# Propulsion_Shield.net
KiCad netlist of a schematic drawn in EAGLE
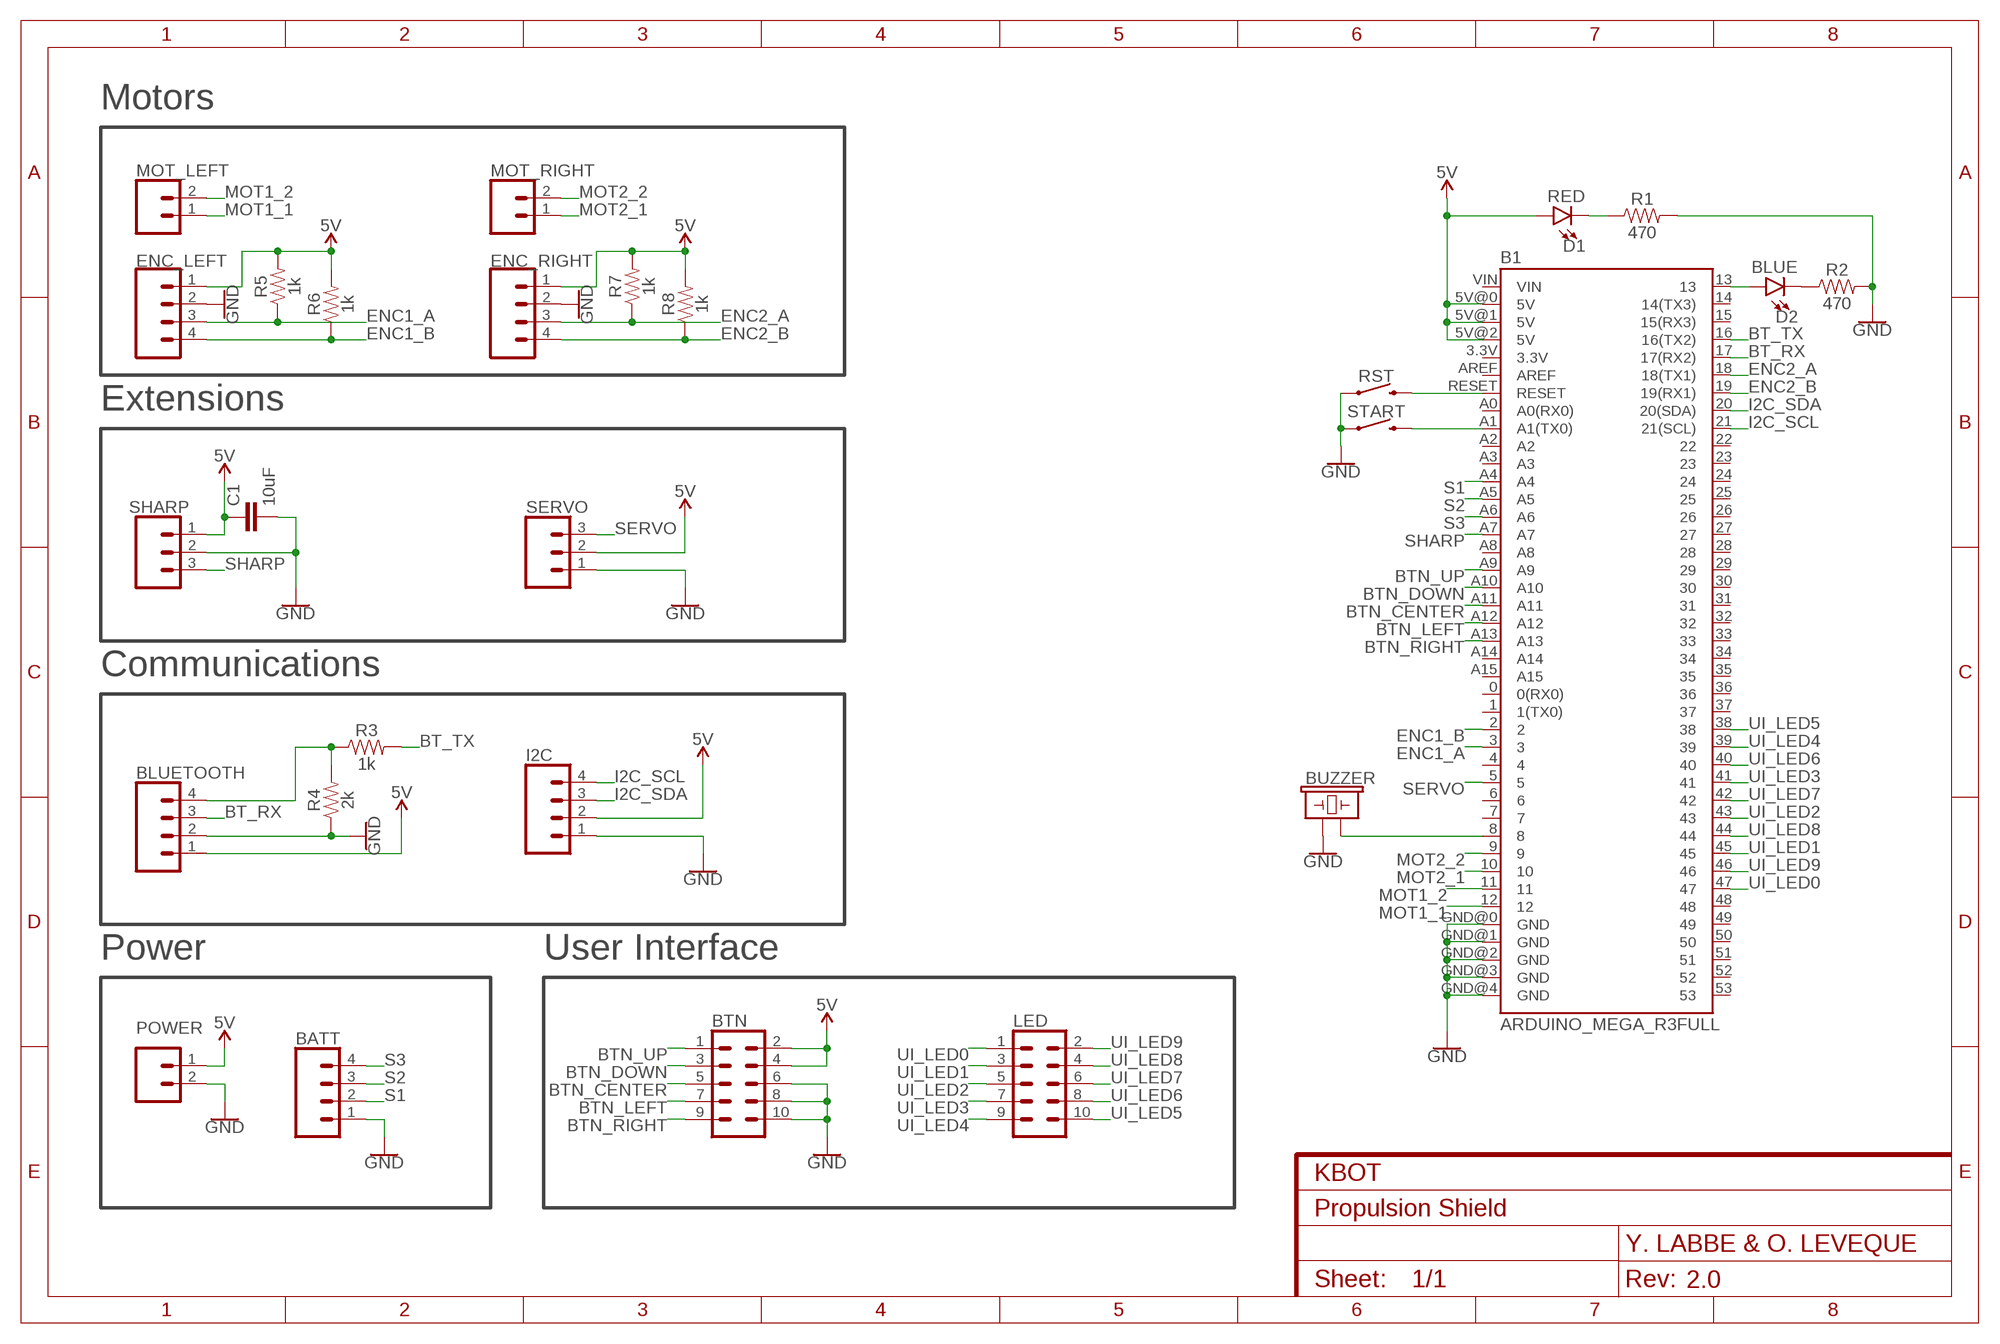
[diagram p0: schematic, sheet 1]

(export (version "E")
  (design (tool "Eeschema 10.0.6"))
  (components
    (comp (ref "B1")
      (value "ARDUINO_MEGA_R3FULL")
      (footprint "eagle-import:ARDUINO_MEGA")
      (libsource (lib "eagle-import") (part "ARDUINO_MEGA_R3FULL"))
    )
    (comp (ref "BATT")
      (value "JST-XH-04-PIN-LONG-PAD")
      (footprint "eagle-import:JST-XH-04-PACKAGE-LONG-PAD")
      (libsource (lib "eagle-import") (part "JST-XH-04-PIN-LONG-PAD"))
    )
    (comp (ref "BLUETOOTH")
      (value "CONN_04")
      (footprint "eagle-import:1X04")
      (libsource (lib "eagle-import") (part "CONN_04"))
    )
    (comp (ref "BTN")
      (value "CONN_05X2SHD")
      (footprint "eagle-import:2X5-SHROUDED")
      (libsource (lib "eagle-import") (part "CONN_05X2SHD"))
    )
    (comp (ref "BUZZER")
      (value "BUZZER-PTH")
      (footprint "eagle-import:BUZZER-12MM")
      (libsource (lib "eagle-import") (part "BUZZER-PTH"))
    )
    (comp (ref "C1")
      (value "10uF")
      (footprint "eagle-import:1206")
      (libsource (lib "eagle-import") (part "10UF-1206-6.3V-20%"))
    )
    (comp (ref "D1")
      (value "RED")
      (footprint "eagle-import:LED-1206")
      (libsource (lib "eagle-import") (part "LED-RED1206"))
    )
    (comp (ref "D2")
      (value "BLUE")
      (footprint "eagle-import:LED-1206")
      (libsource (lib "eagle-import") (part "LED-BLUE1206"))
    )
    (comp (ref "ENC_LEFT")
      (value "JST-XH-04-PIN-LONG-PAD")
      (footprint "eagle-import:JST-XH-04-PACKAGE-LONG-PAD")
      (libsource (lib "eagle-import") (part "JST-XH-04-PIN-LONG-PAD"))
    )
    (comp (ref "ENC_RIGHT")
      (value "JST-XH-04-PIN-LONG-PAD")
      (footprint "eagle-import:JST-XH-04-PACKAGE-LONG-PAD")
      (libsource (lib "eagle-import") (part "JST-XH-04-PIN-LONG-PAD"))
    )
    (comp (ref "I2C")
      (value "CONN_04")
      (footprint "eagle-import:1X04")
      (libsource (lib "eagle-import") (part "CONN_04"))
    )
    (comp (ref "LED")
      (value "CONN_05X2SHD")
      (footprint "eagle-import:2X5-SHROUDED")
      (libsource (lib "eagle-import") (part "CONN_05X2SHD"))
    )
    (comp (ref "MOT_LEFT")
      (value "CONN_02")
      (footprint "eagle-import:1X02")
      (libsource (lib "eagle-import") (part "CONN_02"))
    )
    (comp (ref "MOT_RIGHT")
      (value "CONN_02")
      (footprint "eagle-import:1X02")
      (libsource (lib "eagle-import") (part "CONN_02"))
    )
    (comp (ref "POWER")
      (value "JST-XH-02-PIN-LONG-PAD")
      (footprint "eagle-import:JST-XH-02-PACKAGE-LONG-PAD")
      (libsource (lib "eagle-import") (part "JST-XH-02-PIN-LONG-PAD"))
    )
    (comp (ref "R1")
      (value "470")
      (footprint "eagle-import:1206")
      (libsource (lib "eagle-import") (part "RESISTOR1206"))
    )
    (comp (ref "R2")
      (value "470")
      (footprint "eagle-import:1206")
      (libsource (lib "eagle-import") (part "RESISTOR1206"))
    )
    (comp (ref "R3")
      (value "1k")
      (footprint "eagle-import:1206")
      (libsource (lib "eagle-import") (part "RESISTOR1206"))
    )
    (comp (ref "R4")
      (value "2k")
      (footprint "eagle-import:1206")
      (libsource (lib "eagle-import") (part "RESISTOR1206"))
    )
    (comp (ref "R5")
      (value "1k")
      (footprint "eagle-import:1206")
      (libsource (lib "eagle-import") (part "RESISTOR1206"))
    )
    (comp (ref "R6")
      (value "1k")
      (footprint "eagle-import:1206")
      (libsource (lib "eagle-import") (part "RESISTOR1206"))
    )
    (comp (ref "R7")
      (value "1k")
      (footprint "eagle-import:1206")
      (libsource (lib "eagle-import") (part "RESISTOR1206"))
    )
    (comp (ref "R8")
      (value "1k")
      (footprint "eagle-import:1206")
      (libsource (lib "eagle-import") (part "RESISTOR1206"))
    )
    (comp (ref "RST")
      (value "MOMENTARY-SWITCH-SPST-PTH-6.0MM")
      (footprint "eagle-import:TACTILE_SWITCH_PTH_6.0MM")
      (libsource (lib "eagle-import") (part "MOMENTARY-SWITCH-SPST-PTH-6.0MM"))
    )
    (comp (ref "SERVO")
      (value "CONN_03")
      (footprint "eagle-import:1X03")
      (libsource (lib "eagle-import") (part "CONN_03"))
    )
    (comp (ref "SHARP")
      (value "JST-PH3")
      (footprint "eagle-import:JST-PH3")
      (libsource (lib "eagle-import") (part "JST-PH3"))
    )
    (comp (ref "START")
      (value "MOMENTARY-SWITCH-SPST-PTH-6.0MM")
      (footprint "eagle-import:TACTILE_SWITCH_PTH_6.0MM")
      (libsource (lib "eagle-import") (part "MOMENTARY-SWITCH-SPST-PTH-6.0MM"))
    )
  )
  (nets
    (net (code "1") (name "/BTN_CENTER") (class "Default")
      (node (ref "B1") (pin "A11") (pinfunction "A11_A11") (pintype "bidirectional"))
      (node (ref "BTN") (pin "5") (pinfunction "5_5") (pintype "passive"))
    )
    (net (code "2") (name "/BTN_DOWN") (class "Default")
      (node (ref "B1") (pin "A10") (pinfunction "A10_A10") (pintype "bidirectional"))
      (node (ref "BTN") (pin "3") (pinfunction "3_3") (pintype "passive"))
    )
    (net (code "3") (name "/BTN_LEFT") (class "Default")
      (node (ref "B1") (pin "A12") (pinfunction "A12_A12") (pintype "bidirectional"))
      (node (ref "BTN") (pin "7") (pinfunction "7_7") (pintype "passive"))
    )
    (net (code "4") (name "/BTN_RIGHT") (class "Default")
      (node (ref "B1") (pin "A13") (pinfunction "A13_A13") (pintype "bidirectional"))
      (node (ref "BTN") (pin "9") (pinfunction "9_9") (pintype "passive"))
    )
    (net (code "5") (name "/BTN_UP") (class "Default")
      (node (ref "B1") (pin "A9") (pinfunction "A9_A9") (pintype "bidirectional"))
      (node (ref "BTN") (pin "1") (pinfunction "1_1") (pintype "passive"))
    )
    (net (code "6") (name "/BT_RX") (class "Default")
      (node (ref "B1") (pin "17") (pinfunction "17(RX2)_17") (pintype "bidirectional"))
      (node (ref "BLUETOOTH") (pin "3") (pinfunction "3_3") (pintype "passive"))
    )
    (net (code "7") (name "/BT_TX") (class "Default")
      (node (ref "B1") (pin "16") (pinfunction "16(TX2)_16") (pintype "bidirectional"))
      (node (ref "R3") (pin "2") (pinfunction "2_2") (pintype "passive"))
    )
    (net (code "8") (name "/ENC1_A") (class "Default")
      (node (ref "B1") (pin "3") (pinfunction "3_3") (pintype "bidirectional"))
      (node (ref "ENC_LEFT") (pin "3") (pinfunction "3_3") (pintype "passive"))
      (node (ref "R5") (pin "1") (pinfunction "1_1") (pintype "passive"))
    )
    (net (code "9") (name "/ENC1_B") (class "Default")
      (node (ref "B1") (pin "2") (pinfunction "2_2") (pintype "bidirectional"))
      (node (ref "ENC_LEFT") (pin "4") (pinfunction "4_4") (pintype "passive"))
      (node (ref "R6") (pin "1") (pinfunction "1_1") (pintype "passive"))
    )
    (net (code "10") (name "/ENC2_A") (class "Default")
      (node (ref "B1") (pin "18") (pinfunction "18(TX1)_18") (pintype "bidirectional"))
      (node (ref "ENC_RIGHT") (pin "3") (pinfunction "3_3") (pintype "passive"))
      (node (ref "R7") (pin "1") (pinfunction "1_1") (pintype "passive"))
    )
    (net (code "11") (name "/ENC2_B") (class "Default")
      (node (ref "B1") (pin "19") (pinfunction "19(RX1)_19") (pintype "bidirectional"))
      (node (ref "ENC_RIGHT") (pin "4") (pinfunction "4_4") (pintype "passive"))
      (node (ref "R8") (pin "1") (pinfunction "1_1") (pintype "passive"))
    )
    (net (code "12") (name "/I2C_SCL") (class "Default")
      (node (ref "B1") (pin "21") (pinfunction "21(SCL)_21") (pintype "bidirectional"))
      (node (ref "I2C") (pin "4") (pinfunction "4_4") (pintype "passive"))
    )
    (net (code "13") (name "/I2C_SDA") (class "Default")
      (node (ref "B1") (pin "20") (pinfunction "20(SDA)_20") (pintype "bidirectional"))
      (node (ref "I2C") (pin "3") (pinfunction "3_3") (pintype "passive"))
    )
    (net (code "14") (name "/MOT1_1") (class "Default")
      (node (ref "B1") (pin "12") (pinfunction "12_12") (pintype "bidirectional"))
      (node (ref "MOT_LEFT") (pin "1") (pinfunction "1_1") (pintype "passive"))
    )
    (net (code "15") (name "/MOT1_2") (class "Default")
      (node (ref "B1") (pin "11") (pinfunction "11_11") (pintype "bidirectional"))
      (node (ref "MOT_LEFT") (pin "2") (pinfunction "2_2") (pintype "passive"))
    )
    (net (code "16") (name "/MOT2_1") (class "Default")
      (node (ref "B1") (pin "10") (pinfunction "10_10") (pintype "bidirectional"))
      (node (ref "MOT_RIGHT") (pin "1") (pinfunction "1_1") (pintype "passive"))
    )
    (net (code "17") (name "/MOT2_2") (class "Default")
      (node (ref "B1") (pin "9") (pinfunction "9_9") (pintype "bidirectional"))
      (node (ref "MOT_RIGHT") (pin "2") (pinfunction "2_2") (pintype "passive"))
    )
    (net (code "18") (name "/S1") (class "Default")
      (node (ref "B1") (pin "A4") (pinfunction "A4_A4") (pintype "bidirectional"))
      (node (ref "BATT") (pin "2") (pinfunction "2_2") (pintype "passive"))
    )
    (net (code "19") (name "/S2") (class "Default")
      (node (ref "B1") (pin "A5") (pinfunction "A5_A5") (pintype "bidirectional"))
      (node (ref "BATT") (pin "3") (pinfunction "3_3") (pintype "passive"))
    )
    (net (code "20") (name "/S3") (class "Default")
      (node (ref "B1") (pin "A6") (pinfunction "A6_A6") (pintype "bidirectional"))
      (node (ref "BATT") (pin "4") (pinfunction "4_4") (pintype "passive"))
    )
    (net (code "21") (name "/SERVO") (class "Default")
      (node (ref "B1") (pin "5") (pinfunction "5_5") (pintype "bidirectional"))
      (node (ref "SERVO") (pin "3") (pinfunction "3_3") (pintype "passive"))
    )
    (net (code "22") (name "/SHARP") (class "Default")
      (node (ref "B1") (pin "A7") (pinfunction "A7_A7") (pintype "bidirectional"))
      (node (ref "SHARP") (pin "3") (pinfunction "3_3") (pintype "passive"))
    )
    (net (code "23") (name "/UI_LED0") (class "Default")
      (node (ref "B1") (pin "47") (pinfunction "47_47") (pintype "bidirectional"))
      (node (ref "LED") (pin "1") (pinfunction "1_1") (pintype "passive"))
    )
    (net (code "24") (name "/UI_LED1") (class "Default")
      (node (ref "B1") (pin "45") (pinfunction "45_45") (pintype "bidirectional"))
      (node (ref "LED") (pin "3") (pinfunction "3_3") (pintype "passive"))
    )
    (net (code "25") (name "/UI_LED2") (class "Default")
      (node (ref "B1") (pin "43") (pinfunction "43_43") (pintype "bidirectional"))
      (node (ref "LED") (pin "5") (pinfunction "5_5") (pintype "passive"))
    )
    (net (code "26") (name "/UI_LED3") (class "Default")
      (node (ref "B1") (pin "41") (pinfunction "41_41") (pintype "bidirectional"))
      (node (ref "LED") (pin "7") (pinfunction "7_7") (pintype "passive"))
    )
    (net (code "27") (name "/UI_LED4") (class "Default")
      (node (ref "B1") (pin "39") (pinfunction "39_39") (pintype "bidirectional"))
      (node (ref "LED") (pin "9") (pinfunction "9_9") (pintype "passive"))
    )
    (net (code "28") (name "/UI_LED5") (class "Default")
      (node (ref "B1") (pin "38") (pinfunction "38_38") (pintype "bidirectional"))
      (node (ref "LED") (pin "10") (pinfunction "10_10") (pintype "passive"))
    )
    (net (code "29") (name "/UI_LED6") (class "Default")
      (node (ref "B1") (pin "40") (pinfunction "40_40") (pintype "bidirectional"))
      (node (ref "LED") (pin "8") (pinfunction "8_8") (pintype "passive"))
    )
    (net (code "30") (name "/UI_LED7") (class "Default")
      (node (ref "B1") (pin "42") (pinfunction "42_42") (pintype "bidirectional"))
      (node (ref "LED") (pin "6") (pinfunction "6_6") (pintype "passive"))
    )
    (net (code "31") (name "/UI_LED8") (class "Default")
      (node (ref "B1") (pin "44") (pinfunction "44_44") (pintype "bidirectional"))
      (node (ref "LED") (pin "4") (pinfunction "4_4") (pintype "passive"))
    )
    (net (code "32") (name "/UI_LED9") (class "Default")
      (node (ref "B1") (pin "46") (pinfunction "46_46") (pintype "bidirectional"))
      (node (ref "LED") (pin "2") (pinfunction "2_2") (pintype "passive"))
    )
    (net (code "33") (name "5V") (class "Default")
      (node (ref "B1") (pin "5V@0") (pinfunction "5V_5V@0") (pintype "bidirectional"))
      (node (ref "B1") (pin "5V@1") (pinfunction "5V_5V@1") (pintype "bidirectional"))
      (node (ref "B1") (pin "5V@2") (pinfunction "5V_5V@2") (pintype "bidirectional"))
      (node (ref "BLUETOOTH") (pin "1") (pinfunction "1_1") (pintype "passive"))
      (node (ref "BTN") (pin "2") (pinfunction "2_2") (pintype "passive"))
      (node (ref "BTN") (pin "4") (pinfunction "4_4") (pintype "passive"))
      (node (ref "C1") (pin "1") (pinfunction "1_1") (pintype "passive"))
      (node (ref "D1") (pin "A") (pinfunction "A_A") (pintype "passive"))
      (node (ref "ENC_LEFT") (pin "1") (pinfunction "1_1") (pintype "passive"))
      (node (ref "ENC_RIGHT") (pin "1") (pinfunction "1_1") (pintype "passive"))
      (node (ref "I2C") (pin "2") (pinfunction "2_2") (pintype "passive"))
      (node (ref "POWER") (pin "1") (pinfunction "1_1") (pintype "passive"))
      (node (ref "R5") (pin "2") (pinfunction "2_2") (pintype "passive"))
      (node (ref "R6") (pin "2") (pinfunction "2_2") (pintype "passive"))
      (node (ref "R7") (pin "2") (pinfunction "2_2") (pintype "passive"))
      (node (ref "R8") (pin "2") (pinfunction "2_2") (pintype "passive"))
      (node (ref "SERVO") (pin "2") (pinfunction "2_2") (pintype "passive"))
      (node (ref "SHARP") (pin "1") (pinfunction "1_1") (pintype "passive"))
    )
    (net (code "34") (name "GND") (class "Default")
      (node (ref "B1") (pin "GND@0") (pinfunction "GND_GND@0") (pintype "bidirectional"))
      (node (ref "B1") (pin "GND@1") (pinfunction "GND_GND@1") (pintype "bidirectional"))
      (node (ref "B1") (pin "GND@2") (pinfunction "GND_GND@2") (pintype "bidirectional"))
      (node (ref "B1") (pin "GND@3") (pinfunction "GND_GND@3") (pintype "bidirectional"))
      (node (ref "B1") (pin "GND@4") (pinfunction "GND_GND@4") (pintype "bidirectional"))
      (node (ref "BATT") (pin "1") (pinfunction "1_1") (pintype "passive"))
      (node (ref "BLUETOOTH") (pin "2") (pinfunction "2_2") (pintype "passive"))
      (node (ref "BTN") (pin "10") (pinfunction "10_10") (pintype "passive"))
      (node (ref "BTN") (pin "6") (pinfunction "6_6") (pintype "passive"))
      (node (ref "BTN") (pin "8") (pinfunction "8_8") (pintype "passive"))
      (node (ref "BUZZER") (pin "+") (pinfunction "1_+") (pintype "passive"))
      (node (ref "C1") (pin "2") (pinfunction "2_2") (pintype "passive"))
      (node (ref "ENC_LEFT") (pin "2") (pinfunction "2_2") (pintype "passive"))
      (node (ref "ENC_RIGHT") (pin "2") (pinfunction "2_2") (pintype "passive"))
      (node (ref "I2C") (pin "1") (pinfunction "1_1") (pintype "passive"))
      (node (ref "POWER") (pin "2") (pinfunction "2_2") (pintype "passive"))
      (node (ref "R1") (pin "2") (pinfunction "2_2") (pintype "passive"))
      (node (ref "R2") (pin "2") (pinfunction "2_2") (pintype "passive"))
      (node (ref "R4") (pin "1") (pinfunction "1_1") (pintype "passive"))
      (node (ref "RST") (pin "1") (pinfunction "1_1") (pintype "passive"))
      (node (ref "SERVO") (pin "1") (pinfunction "1_1") (pintype "passive"))
      (node (ref "SHARP") (pin "2") (pinfunction "2_2") (pintype "passive"))
      (node (ref "START") (pin "1") (pinfunction "1_1") (pintype "passive"))
    )
    (net (code "35") (name "Net-(B1-A1(TX0))") (class "Default")
      (node (ref "B1") (pin "A1") (pinfunction "A1(TX0)_A1") (pintype "bidirectional"))
      (node (ref "START") (pin "3") (pinfunction "2_3") (pintype "passive"))
    )
    (net (code "36") (name "Net-(B1-Pad13)") (class "Default")
      (node (ref "B1") (pin "13") (pinfunction "13_13") (pintype "bidirectional"))
      (node (ref "D2") (pin "A") (pinfunction "A_A") (pintype "passive"))
    )
    (net (code "37") (name "Net-(BLUETOOTH-Pad4)") (class "Default")
      (node (ref "BLUETOOTH") (pin "4") (pinfunction "4_4") (pintype "passive"))
      (node (ref "R3") (pin "1") (pinfunction "1_1") (pintype "passive"))
      (node (ref "R4") (pin "2") (pinfunction "2_2") (pintype "passive"))
    )
    (net (code "38") (name "Net-(BUZZER-2)") (class "Default")
      (node (ref "B1") (pin "8") (pinfunction "8_8") (pintype "bidirectional"))
      (node (ref "BUZZER") (pin "-") (pinfunction "2_-") (pintype "passive"))
    )
    (net (code "39") (name "Net-(D1-PadC)") (class "Default")
      (node (ref "D1") (pin "C") (pinfunction "C_C") (pintype "passive"))
      (node (ref "R1") (pin "1") (pinfunction "1_1") (pintype "passive"))
    )
    (net (code "40") (name "Net-(D2-PadC)") (class "Default")
      (node (ref "D2") (pin "C") (pinfunction "C_C") (pintype "passive"))
      (node (ref "R2") (pin "1") (pinfunction "1_1") (pintype "passive"))
    )
    (net (code "41") (name "Net-(RST-2)") (class "Default")
      (node (ref "B1") (pin "RESET") (pinfunction "RESET_RESET") (pintype "bidirectional"))
      (node (ref "RST") (pin "3") (pinfunction "2_3") (pintype "passive"))
    )
    (net (code "42") (name "unconnected-(B1-0(RX0)-Pad0)") (class "Default")
      (node (ref "B1") (pin "0") (pinfunction "0(RX0)_0") (pintype "bidirectional"))
    )
    (net (code "43") (name "unconnected-(B1-1(TX0)-Pad1)") (class "Default")
      (node (ref "B1") (pin "1") (pinfunction "1(TX0)_1") (pintype "bidirectional"))
    )
    (net (code "44") (name "unconnected-(B1-14(TX3)-Pad14)") (class "Default")
      (node (ref "B1") (pin "14") (pinfunction "14(TX3)_14") (pintype "bidirectional"))
    )
    (net (code "45") (name "unconnected-(B1-15(RX3)-Pad15)") (class "Default")
      (node (ref "B1") (pin "15") (pinfunction "15(RX3)_15") (pintype "bidirectional"))
    )
    (net (code "46") (name "unconnected-(B1-A0(RX0)-PadA0)") (class "Default")
      (node (ref "B1") (pin "A0") (pinfunction "A0(RX0)_A0") (pintype "bidirectional"))
    )
    (net (code "47") (name "unconnected-(B1-Pad3.3V)") (class "Default")
      (node (ref "B1") (pin "3.3V") (pinfunction "3.3V_3.3V") (pintype "bidirectional"))
    )
    (net (code "48") (name "unconnected-(B1-Pad4)") (class "Default")
      (node (ref "B1") (pin "4") (pinfunction "4_4") (pintype "bidirectional"))
    )
    (net (code "49") (name "unconnected-(B1-Pad6)") (class "Default")
      (node (ref "B1") (pin "6") (pinfunction "6_6") (pintype "bidirectional"))
    )
    (net (code "50") (name "unconnected-(B1-Pad7)") (class "Default")
      (node (ref "B1") (pin "7") (pinfunction "7_7") (pintype "bidirectional"))
    )
    (net (code "51") (name "unconnected-(B1-Pad22)") (class "Default")
      (node (ref "B1") (pin "22") (pinfunction "22_22") (pintype "bidirectional"))
    )
    (net (code "52") (name "unconnected-(B1-Pad23)") (class "Default")
      (node (ref "B1") (pin "23") (pinfunction "23_23") (pintype "bidirectional"))
    )
    (net (code "53") (name "unconnected-(B1-Pad24)") (class "Default")
      (node (ref "B1") (pin "24") (pinfunction "24_24") (pintype "bidirectional"))
    )
    (net (code "54") (name "unconnected-(B1-Pad25)") (class "Default")
      (node (ref "B1") (pin "25") (pinfunction "25_25") (pintype "bidirectional"))
    )
    (net (code "55") (name "unconnected-(B1-Pad26)") (class "Default")
      (node (ref "B1") (pin "26") (pinfunction "26_26") (pintype "bidirectional"))
    )
    (net (code "56") (name "unconnected-(B1-Pad27)") (class "Default")
      (node (ref "B1") (pin "27") (pinfunction "27_27") (pintype "bidirectional"))
    )
    (net (code "57") (name "unconnected-(B1-Pad28)") (class "Default")
      (node (ref "B1") (pin "28") (pinfunction "28_28") (pintype "bidirectional"))
    )
    (net (code "58") (name "unconnected-(B1-Pad29)") (class "Default")
      (node (ref "B1") (pin "29") (pinfunction "29_29") (pintype "bidirectional"))
    )
    (net (code "59") (name "unconnected-(B1-Pad30)") (class "Default")
      (node (ref "B1") (pin "30") (pinfunction "30_30") (pintype "bidirectional"))
    )
    (net (code "60") (name "unconnected-(B1-Pad31)") (class "Default")
      (node (ref "B1") (pin "31") (pinfunction "31_31") (pintype "bidirectional"))
    )
    (net (code "61") (name "unconnected-(B1-Pad32)") (class "Default")
      (node (ref "B1") (pin "32") (pinfunction "32_32") (pintype "bidirectional"))
    )
    (net (code "62") (name "unconnected-(B1-Pad33)") (class "Default")
      (node (ref "B1") (pin "33") (pinfunction "33_33") (pintype "bidirectional"))
    )
    (net (code "63") (name "unconnected-(B1-Pad34)") (class "Default")
      (node (ref "B1") (pin "34") (pinfunction "34_34") (pintype "bidirectional"))
    )
    (net (code "64") (name "unconnected-(B1-Pad35)") (class "Default")
      (node (ref "B1") (pin "35") (pinfunction "35_35") (pintype "bidirectional"))
    )
    (net (code "65") (name "unconnected-(B1-Pad36)") (class "Default")
      (node (ref "B1") (pin "36") (pinfunction "36_36") (pintype "bidirectional"))
    )
    (net (code "66") (name "unconnected-(B1-Pad37)") (class "Default")
      (node (ref "B1") (pin "37") (pinfunction "37_37") (pintype "bidirectional"))
    )
    (net (code "67") (name "unconnected-(B1-Pad48)") (class "Default")
      (node (ref "B1") (pin "48") (pinfunction "48_48") (pintype "bidirectional"))
    )
    (net (code "68") (name "unconnected-(B1-Pad49)") (class "Default")
      (node (ref "B1") (pin "49") (pinfunction "49_49") (pintype "bidirectional"))
    )
    (net (code "69") (name "unconnected-(B1-Pad50)") (class "Default")
      (node (ref "B1") (pin "50") (pinfunction "50_50") (pintype "bidirectional"))
    )
    (net (code "70") (name "unconnected-(B1-Pad51)") (class "Default")
      (node (ref "B1") (pin "51") (pinfunction "51_51") (pintype "bidirectional"))
    )
    (net (code "71") (name "unconnected-(B1-Pad52)") (class "Default")
      (node (ref "B1") (pin "52") (pinfunction "52_52") (pintype "bidirectional"))
    )
    (net (code "72") (name "unconnected-(B1-Pad53)") (class "Default")
      (node (ref "B1") (pin "53") (pinfunction "53_53") (pintype "bidirectional"))
    )
    (net (code "73") (name "unconnected-(B1-PadA2)") (class "Default")
      (node (ref "B1") (pin "A2") (pinfunction "A2_A2") (pintype "bidirectional"))
    )
    (net (code "74") (name "unconnected-(B1-PadA3)") (class "Default")
      (node (ref "B1") (pin "A3") (pinfunction "A3_A3") (pintype "bidirectional"))
    )
    (net (code "75") (name "unconnected-(B1-PadA8)") (class "Default")
      (node (ref "B1") (pin "A8") (pinfunction "A8_A8") (pintype "bidirectional"))
    )
    (net (code "76") (name "unconnected-(B1-PadA14)") (class "Default")
      (node (ref "B1") (pin "A14") (pinfunction "A14_A14") (pintype "bidirectional"))
    )
    (net (code "77") (name "unconnected-(B1-PadA15)") (class "Default")
      (node (ref "B1") (pin "A15") (pinfunction "A15_A15") (pintype "bidirectional"))
    )
    (net (code "78") (name "unconnected-(B1-PadAREF)") (class "Default")
      (node (ref "B1") (pin "AREF") (pinfunction "AREF_AREF") (pintype "bidirectional"))
    )
    (net (code "79") (name "unconnected-(B1-PadVIN)") (class "Default")
      (node (ref "B1") (pin "VIN") (pinfunction "VIN_VIN") (pintype "bidirectional"))
    )
  )
)
